# 35_STM32.net
KiCad netlist of a schematic drawn in Altium Designer
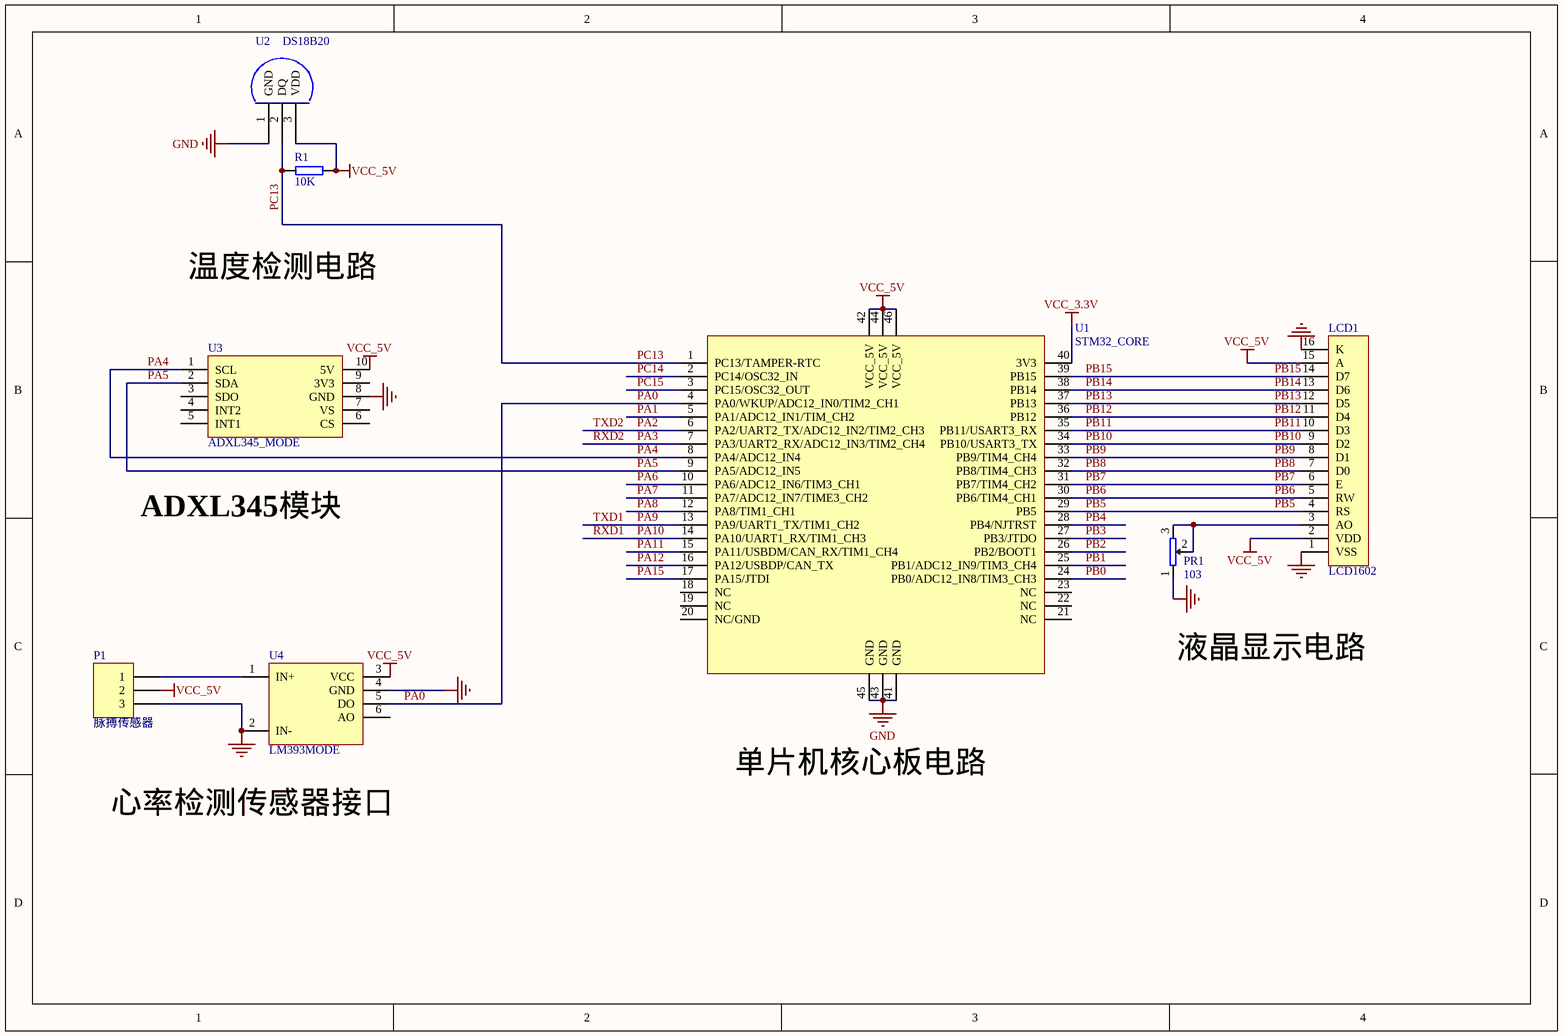
[diagram p0: 35、基于STM32单片机智能手环心率计步器体温显示设计.SchDoc]

(export (version "E")
  (design (tool "Eeschema 10.0.6"))
  (components
    (comp (ref "LCD1")
      (value "LCD1602")
      (footprint "LCD1602")
      (description "LCD1602液晶")
      (libsource (lib "参考") (part "LCD1602"))
    )
    (comp (ref "P1")
      (value "脉搏传感器")
      (footprint "心率MODE")
      (fields (field (name "PUBLISHER") "Altium Limited"))
      (libsource (lib "参考") (part "脉搏传感器"))
    )
    (comp (ref "PR1")
      (value "103")
      (footprint "WH06-2")
      (description "电位器")
      (libsource (lib "参考") (part "PR"))
    )
    (comp (ref "R1")
      (value "10K")
      (footprint "AXIAL0.3")
      (description "电阻")
      (libsource (lib "参考") (part "RES"))
    )
    (comp (ref "U1")
      (value "STM32_CORE")
      (footprint "STM32_CORE")
      (description "STM32核心板")
      (libsource (lib "参考") (part "STM32_CORE"))
    )
    (comp (ref "U2")
      (value "DS18B20")
      (footprint "TO-92")
      (description "DS18B20温度芯片")
      (libsource (lib "参考") (part "DS18B20"))
    )
    (comp (ref "U3")
      (value "ADXL345_MODE")
      (footprint "ADXL345MODE")
      (description "ADXL345 倾斜模块")
      (libsource (lib "参考") (part "ADXL345_MODE"))
    )
    (comp (ref "U4")
      (value "LM393MODE")
      (footprint "LM393MODE")
      (description "LM393比较器芯片")
      (libsource (lib "参考") (part "LM393MODE"))
    )
  )
  (nets
    (net (code "1") (name "/PA0") (class "Default")
      (node (ref "U1") (pin "4") (pinfunction "PA0/WKUP/ADC12_IN0/TIM2_CH1_4") (pintype "passive"))
      (node (ref "U4") (pin "5") (pinfunction "DO_5") (pintype "passive"))
    )
    (net (code "2") (name "/PA1") (class "Default")
      (node (ref "U1") (pin "5") (pinfunction "PA1/ADC12_IN1/TIM_CH2_5") (pintype "passive"))
    )
    (net (code "3") (name "/PA2") (class "Default")
      (node (ref "U1") (pin "6") (pinfunction "PA2/UART2_TX/ADC12_IN2/TIM2_CH3_6") (pintype "passive"))
    )
    (net (code "4") (name "/PA3") (class "Default")
      (node (ref "U1") (pin "7") (pinfunction "PA3/UART2_RX/ADC12_IN3/TIM2_CH4_7") (pintype "passive"))
    )
    (net (code "5") (name "/PA4") (class "Default")
      (node (ref "U1") (pin "8") (pinfunction "PA4/ADC12_IN4_8") (pintype "passive"))
      (node (ref "U3") (pin "1") (pinfunction "SCL_1") (pintype "passive"))
    )
    (net (code "6") (name "/PA5") (class "Default")
      (node (ref "U1") (pin "9") (pinfunction "PA5/ADC12_IN5_9") (pintype "passive"))
      (node (ref "U3") (pin "2") (pinfunction "SDA_2") (pintype "passive"))
    )
    (net (code "7") (name "/PA6") (class "Default")
      (node (ref "U1") (pin "10") (pinfunction "PA6/ADC12_IN6/TIM3_CH1_10") (pintype "passive"))
    )
    (net (code "8") (name "/PA7") (class "Default")
      (node (ref "U1") (pin "11") (pinfunction "PA7/ADC12_IN7/TIME3_CH2_11") (pintype "passive"))
    )
    (net (code "9") (name "/PA8") (class "Default")
      (node (ref "U1") (pin "12") (pinfunction "PA8/TIM1_CH1_12") (pintype "passive"))
    )
    (net (code "10") (name "/PA9") (class "Default")
      (node (ref "U1") (pin "13") (pinfunction "PA9/UART1_TX/TIM1_CH2_13") (pintype "passive"))
    )
    (net (code "11") (name "/PA10") (class "Default")
      (node (ref "U1") (pin "14") (pinfunction "PA10/UART1_RX/TIM1_CH3_14") (pintype "passive"))
    )
    (net (code "12") (name "/PA11") (class "Default")
      (node (ref "U1") (pin "15") (pinfunction "PA11/USBDM/CAN_RX/TIM1_CH4_15") (pintype "passive"))
    )
    (net (code "13") (name "/PA12") (class "Default")
      (node (ref "U1") (pin "16") (pinfunction "PA12/USBDP/CAN_TX_16") (pintype "passive"))
    )
    (net (code "14") (name "/PA15") (class "Default")
      (node (ref "U1") (pin "17") (pinfunction "PA15/JTDI_17") (pintype "passive"))
    )
    (net (code "15") (name "/PB0") (class "Default")
      (node (ref "U1") (pin "24") (pinfunction "PB0/ADC12_IN8/TIM3_CH3_24") (pintype "passive"))
    )
    (net (code "16") (name "/PB1") (class "Default")
      (node (ref "U1") (pin "25") (pinfunction "PB1/ADC12_IN9/TIM3_CH4_25") (pintype "passive"))
    )
    (net (code "17") (name "/PB2") (class "Default")
      (node (ref "U1") (pin "26") (pinfunction "PB2/BOOT1_26") (pintype "passive"))
    )
    (net (code "18") (name "/PB3") (class "Default")
      (node (ref "U1") (pin "27") (pinfunction "PB3/JTDO_27") (pintype "passive"))
    )
    (net (code "19") (name "/PB4") (class "Default")
      (node (ref "U1") (pin "28") (pinfunction "PB4/NJTRST_28") (pintype "passive"))
    )
    (net (code "20") (name "/PB5") (class "Default")
      (node (ref "LCD1") (pin "4") (pinfunction "RS_4") (pintype "passive"))
      (node (ref "U1") (pin "29") (pinfunction "PB5_29") (pintype "passive"))
    )
    (net (code "21") (name "/PB6") (class "Default")
      (node (ref "LCD1") (pin "5") (pinfunction "RW_5") (pintype "passive"))
      (node (ref "U1") (pin "30") (pinfunction "PB6/TIM4_CH1_30") (pintype "passive"))
    )
    (net (code "22") (name "/PB7") (class "Default")
      (node (ref "LCD1") (pin "6") (pinfunction "E_6") (pintype "passive"))
      (node (ref "U1") (pin "31") (pinfunction "PB7/TIM4_CH2_31") (pintype "passive"))
    )
    (net (code "23") (name "/PB8") (class "Default")
      (node (ref "LCD1") (pin "7") (pinfunction "D0_7") (pintype "passive"))
      (node (ref "U1") (pin "32") (pinfunction "PB8/TIM4_CH3_32") (pintype "passive"))
    )
    (net (code "24") (name "/PB9") (class "Default")
      (node (ref "LCD1") (pin "8") (pinfunction "D1_8") (pintype "passive"))
      (node (ref "U1") (pin "33") (pinfunction "PB9/TIM4_CH4_33") (pintype "passive"))
    )
    (net (code "25") (name "/PB10") (class "Default")
      (node (ref "LCD1") (pin "9") (pinfunction "D2_9") (pintype "passive"))
      (node (ref "U1") (pin "34") (pinfunction "PB10/USART3_TX_34") (pintype "passive"))
    )
    (net (code "26") (name "/PB11") (class "Default")
      (node (ref "LCD1") (pin "10") (pinfunction "D3_10") (pintype "passive"))
      (node (ref "U1") (pin "35") (pinfunction "PB11/USART3_RX_35") (pintype "passive"))
    )
    (net (code "27") (name "/PB12") (class "Default")
      (node (ref "LCD1") (pin "11") (pinfunction "D4_11") (pintype "passive"))
      (node (ref "U1") (pin "36") (pinfunction "PB12_36") (pintype "passive"))
    )
    (net (code "28") (name "/PB13") (class "Default")
      (node (ref "LCD1") (pin "12") (pinfunction "D5_12") (pintype "passive"))
      (node (ref "U1") (pin "37") (pinfunction "PB13_37") (pintype "passive"))
    )
    (net (code "29") (name "/PB14") (class "Default")
      (node (ref "LCD1") (pin "13") (pinfunction "D6_13") (pintype "passive"))
      (node (ref "U1") (pin "38") (pinfunction "PB14_38") (pintype "passive"))
    )
    (net (code "30") (name "/PB15") (class "Default")
      (node (ref "LCD1") (pin "14") (pinfunction "D7_14") (pintype "passive"))
      (node (ref "U1") (pin "39") (pinfunction "PB15_39") (pintype "passive"))
    )
    (net (code "31") (name "/PC13") (class "Default")
      (node (ref "R1") (pin "1") (pinfunction "1_1") (pintype "passive"))
      (node (ref "U1") (pin "1") (pinfunction "PC13/TAMPER-RTC_1") (pintype "passive"))
      (node (ref "U2") (pin "2") (pinfunction "DQ_2") (pintype "power_in"))
    )
    (net (code "32") (name "/PC14") (class "Default")
      (node (ref "U1") (pin "2") (pinfunction "PC14/OSC32_IN_2") (pintype "passive"))
    )
    (net (code "33") (name "/PC15") (class "Default")
      (node (ref "U1") (pin "3") (pinfunction "PC15/OSC32_OUT_3") (pintype "passive"))
    )
    (net (code "34") (name "GND") (class "Default")
      (node (ref "LCD1") (pin "1") (pinfunction "VSS_1") (pintype "passive"))
      (node (ref "LCD1") (pin "16") (pinfunction "K_16") (pintype "passive"))
      (node (ref "P1") (pin "3") (pinfunction "3_3") (pintype "passive"))
      (node (ref "PR1") (pin "1") (pinfunction "1_1") (pintype "passive"))
      (node (ref "U1") (pin "41") (pinfunction "GND_41") (pintype "passive"))
      (node (ref "U1") (pin "43") (pinfunction "GND_43") (pintype "passive"))
      (node (ref "U1") (pin "45") (pinfunction "GND_45") (pintype "passive"))
      (node (ref "U2") (pin "1") (pinfunction "GND_1") (pintype "power_in"))
      (node (ref "U3") (pin "8") (pinfunction "GND_8") (pintype "passive"))
      (node (ref "U4") (pin "2") (pinfunction "IN-_2") (pintype "passive"))
      (node (ref "U4") (pin "4") (pinfunction "GND_4") (pintype "passive"))
    )
    (net (code "35") (name "Net-(LCD1-AO)") (class "Default")
      (node (ref "LCD1") (pin "3") (pinfunction "AO_3") (pintype "passive"))
      (node (ref "PR1") (pin "2") (pinfunction "2_2") (pintype "passive"))
      (node (ref "PR1") (pin "3") (pinfunction "3_3") (pintype "passive"))
    )
    (net (code "36") (name "Net-(U4-IN+)") (class "Default")
      (node (ref "P1") (pin "1") (pinfunction "1_1") (pintype "passive"))
      (node (ref "U4") (pin "1") (pinfunction "IN+_1") (pintype "passive"))
    )
    (net (code "37") (name "VCC_3.3V") (class "Default")
      (node (ref "U1") (pin "40") (pinfunction "3V3_40") (pintype "passive"))
    )
    (net (code "38") (name "VCC_5V") (class "Default")
      (node (ref "LCD1") (pin "15") (pinfunction "A_15") (pintype "passive"))
      (node (ref "LCD1") (pin "2") (pinfunction "VDD_2") (pintype "passive"))
      (node (ref "P1") (pin "2") (pinfunction "2_2") (pintype "passive"))
      (node (ref "R1") (pin "2") (pinfunction "2_2") (pintype "passive"))
      (node (ref "U1") (pin "42") (pinfunction "VCC_5V_42") (pintype "passive"))
      (node (ref "U1") (pin "44") (pinfunction "VCC_5V_44") (pintype "passive"))
      (node (ref "U1") (pin "46") (pinfunction "VCC_5V_46") (pintype "passive"))
      (node (ref "U2") (pin "3") (pinfunction "VDD_3") (pintype "power_in"))
      (node (ref "U3") (pin "10") (pinfunction "5V_10") (pintype "passive"))
      (node (ref "U4") (pin "3") (pinfunction "VCC_3") (pintype "passive"))
    )
    (net (code "39") (name "unconnected-(U1-NC-Pad18)") (class "Default")
      (node (ref "U1") (pin "18") (pinfunction "NC_18") (pintype "passive"))
    )
    (net (code "40") (name "unconnected-(U1-NC-Pad19)") (class "Default")
      (node (ref "U1") (pin "19") (pinfunction "NC_19") (pintype "passive"))
    )
    (net (code "41") (name "unconnected-(U1-NC-Pad21)") (class "Default")
      (node (ref "U1") (pin "21") (pinfunction "NC_21") (pintype "passive"))
    )
    (net (code "42") (name "unconnected-(U1-NC-Pad22)") (class "Default")
      (node (ref "U1") (pin "22") (pinfunction "NC_22") (pintype "passive"))
    )
    (net (code "43") (name "unconnected-(U1-NC-Pad23)") (class "Default")
      (node (ref "U1") (pin "23") (pinfunction "NC_23") (pintype "passive"))
    )
    (net (code "44") (name "unconnected-(U1-NC{slash}GND-Pad20)") (class "Default")
      (node (ref "U1") (pin "20") (pinfunction "NC/GND_20") (pintype "passive"))
    )
    (net (code "45") (name "unconnected-(U3-3V3-Pad9)") (class "Default")
      (node (ref "U3") (pin "9") (pinfunction "3V3_9") (pintype "passive"))
    )
    (net (code "46") (name "unconnected-(U3-CS-Pad6)") (class "Default")
      (node (ref "U3") (pin "6") (pinfunction "CS_6") (pintype "passive"))
    )
    (net (code "47") (name "unconnected-(U3-INT1-Pad5)") (class "Default")
      (node (ref "U3") (pin "5") (pinfunction "INT1_5") (pintype "passive"))
    )
    (net (code "48") (name "unconnected-(U3-INT2-Pad4)") (class "Default")
      (node (ref "U3") (pin "4") (pinfunction "INT2_4") (pintype "passive"))
    )
    (net (code "49") (name "unconnected-(U3-SDO-Pad3)") (class "Default")
      (node (ref "U3") (pin "3") (pinfunction "SDO_3") (pintype "passive"))
    )
    (net (code "50") (name "unconnected-(U3-VS-Pad7)") (class "Default")
      (node (ref "U3") (pin "7") (pinfunction "VS_7") (pintype "passive"))
    )
    (net (code "51") (name "unconnected-(U4-AO-Pad6)") (class "Default")
      (node (ref "U4") (pin "6") (pinfunction "AO_6") (pintype "passive"))
    )
  )
)
